# Reactor_Core.net
KiCad netlist of a schematic drawn in EAGLE
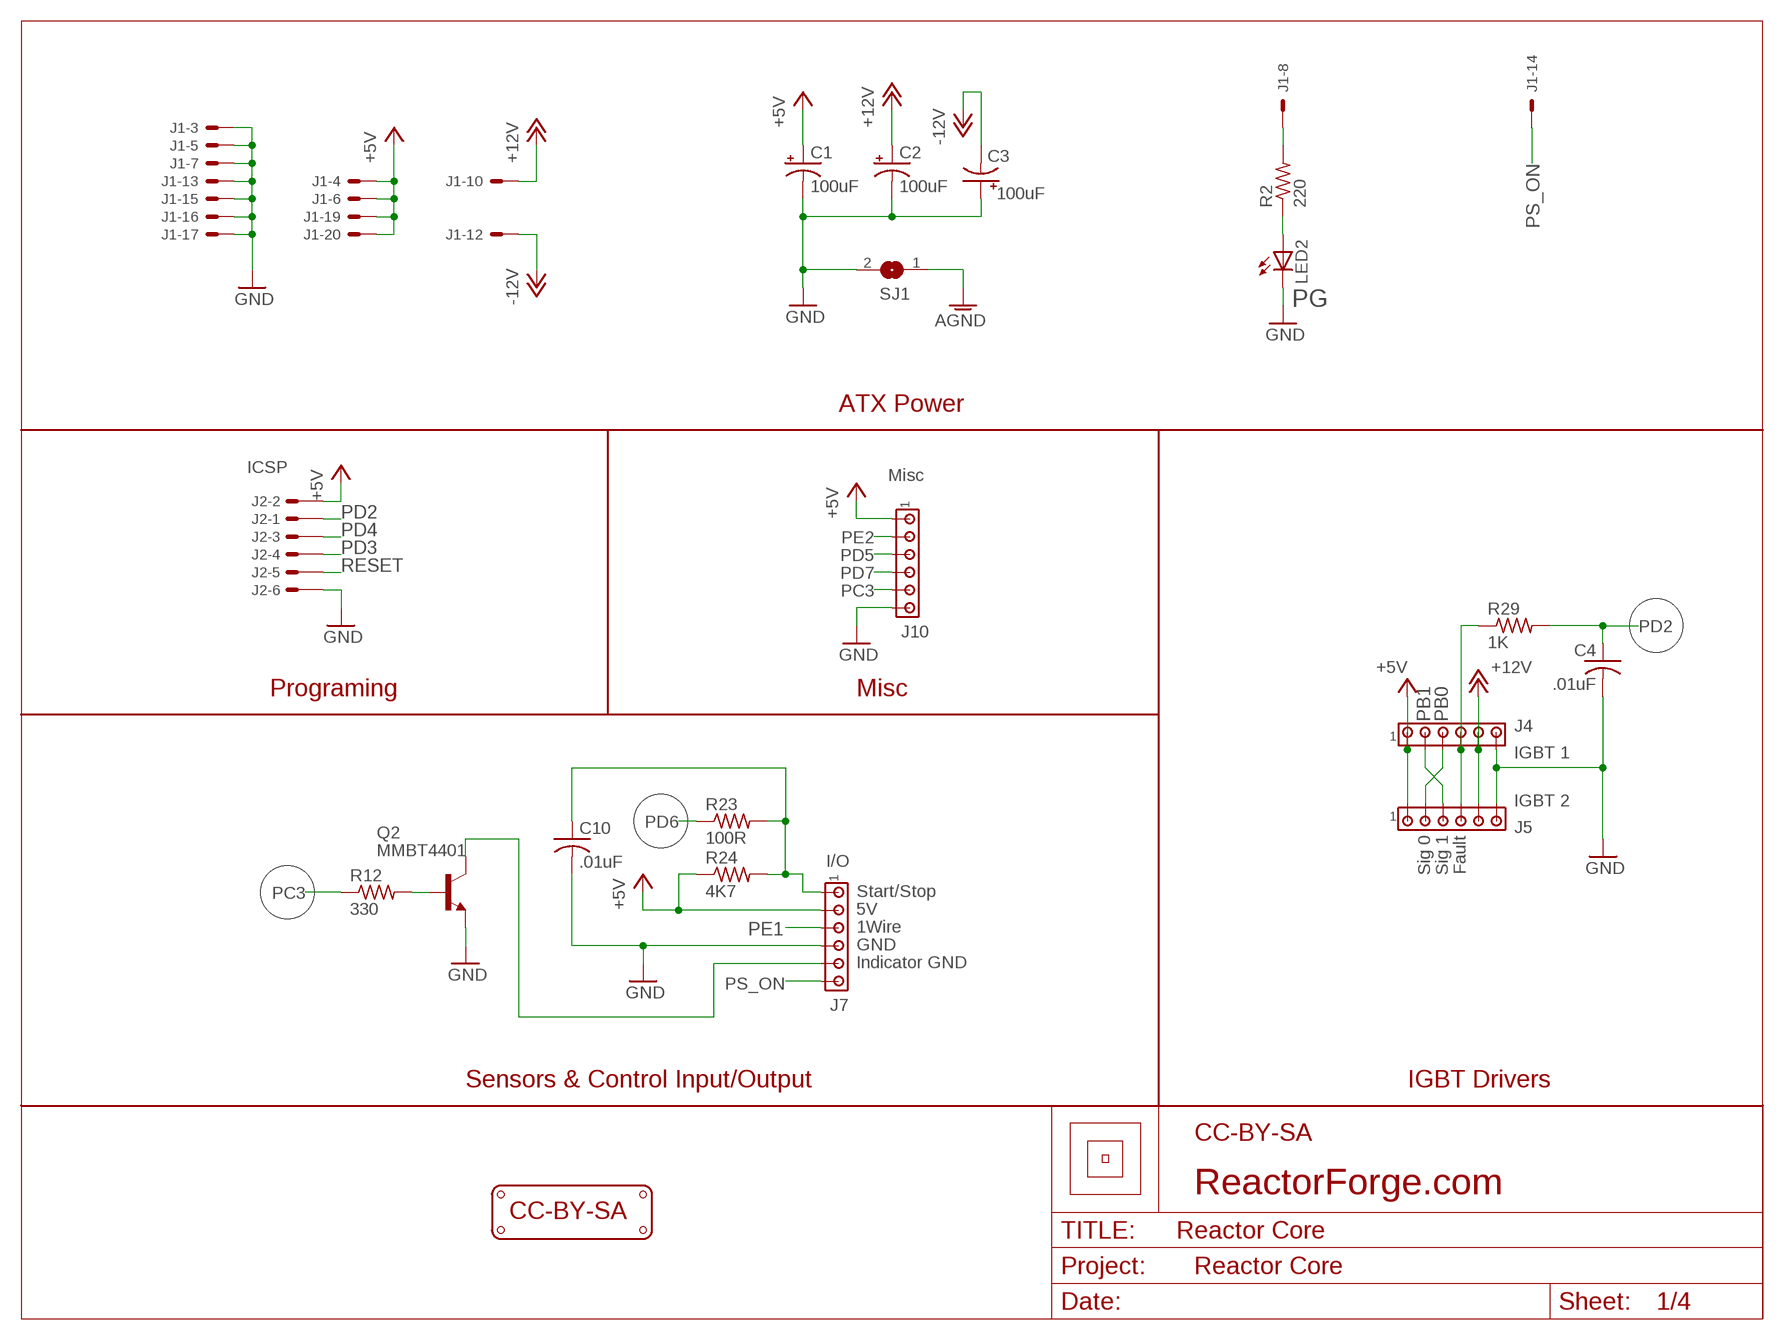
[diagram p0: schematic, sheet 1]
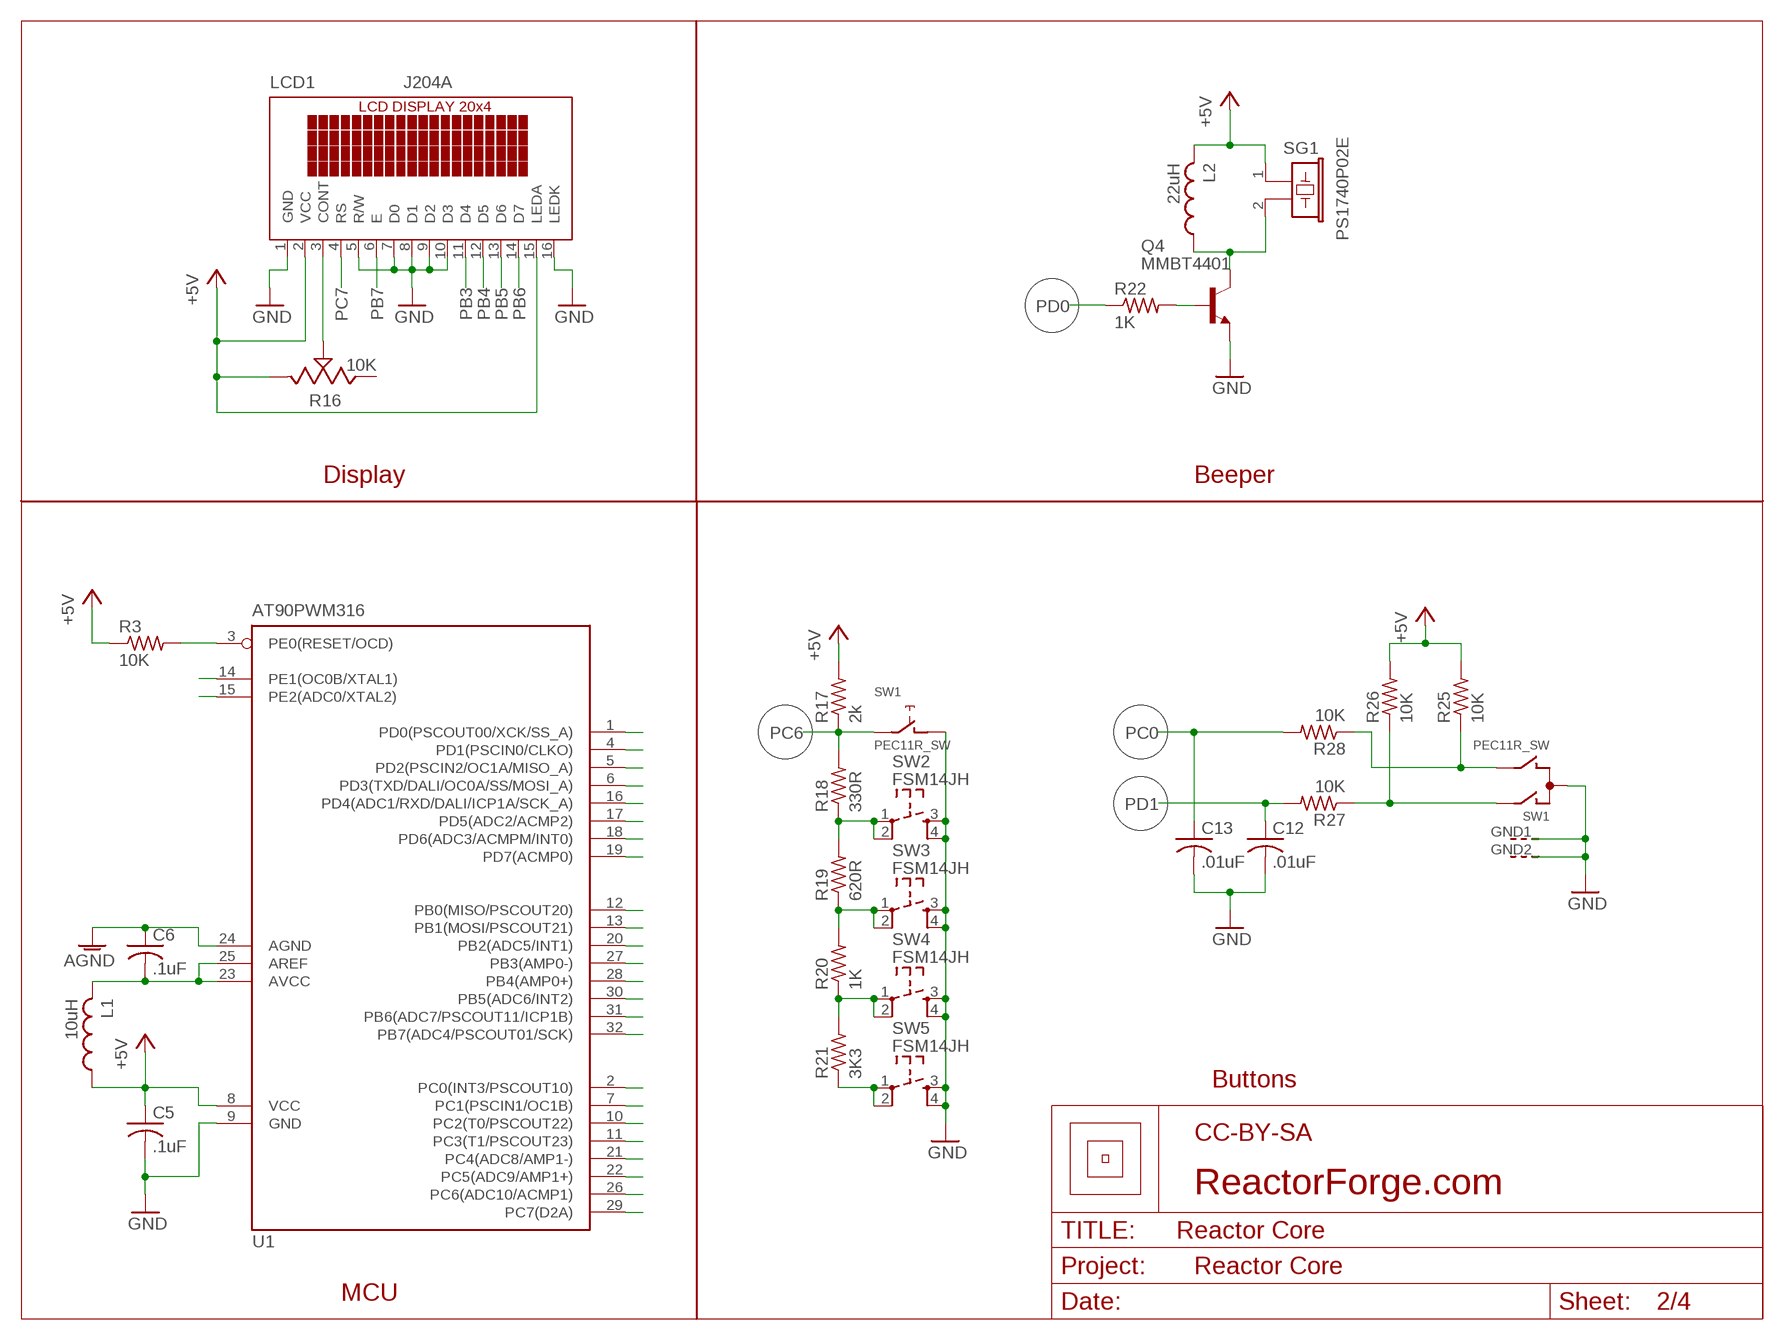
[diagram p1: schematic, sheet 2]
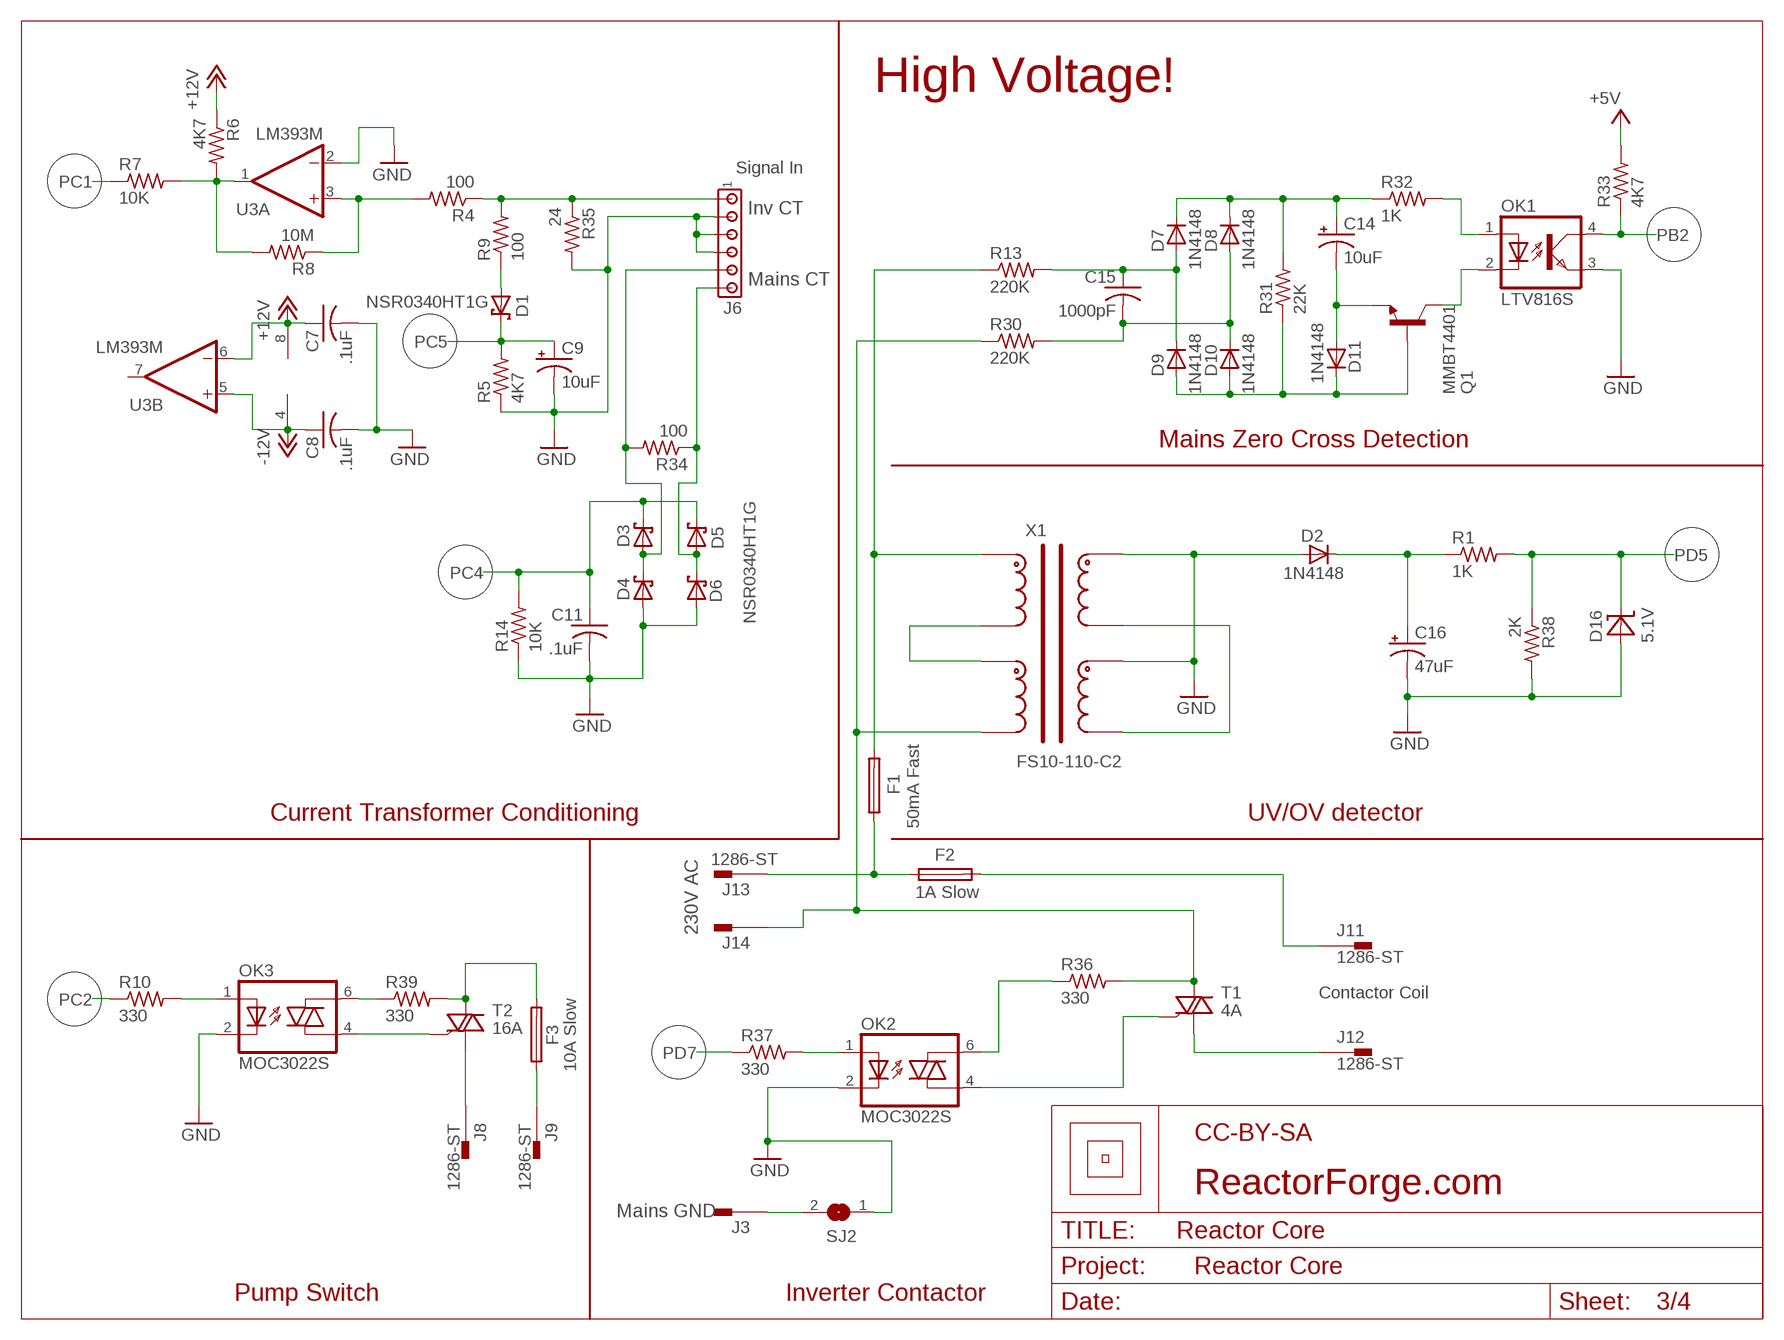
[diagram p2: schematic, sheet 3]
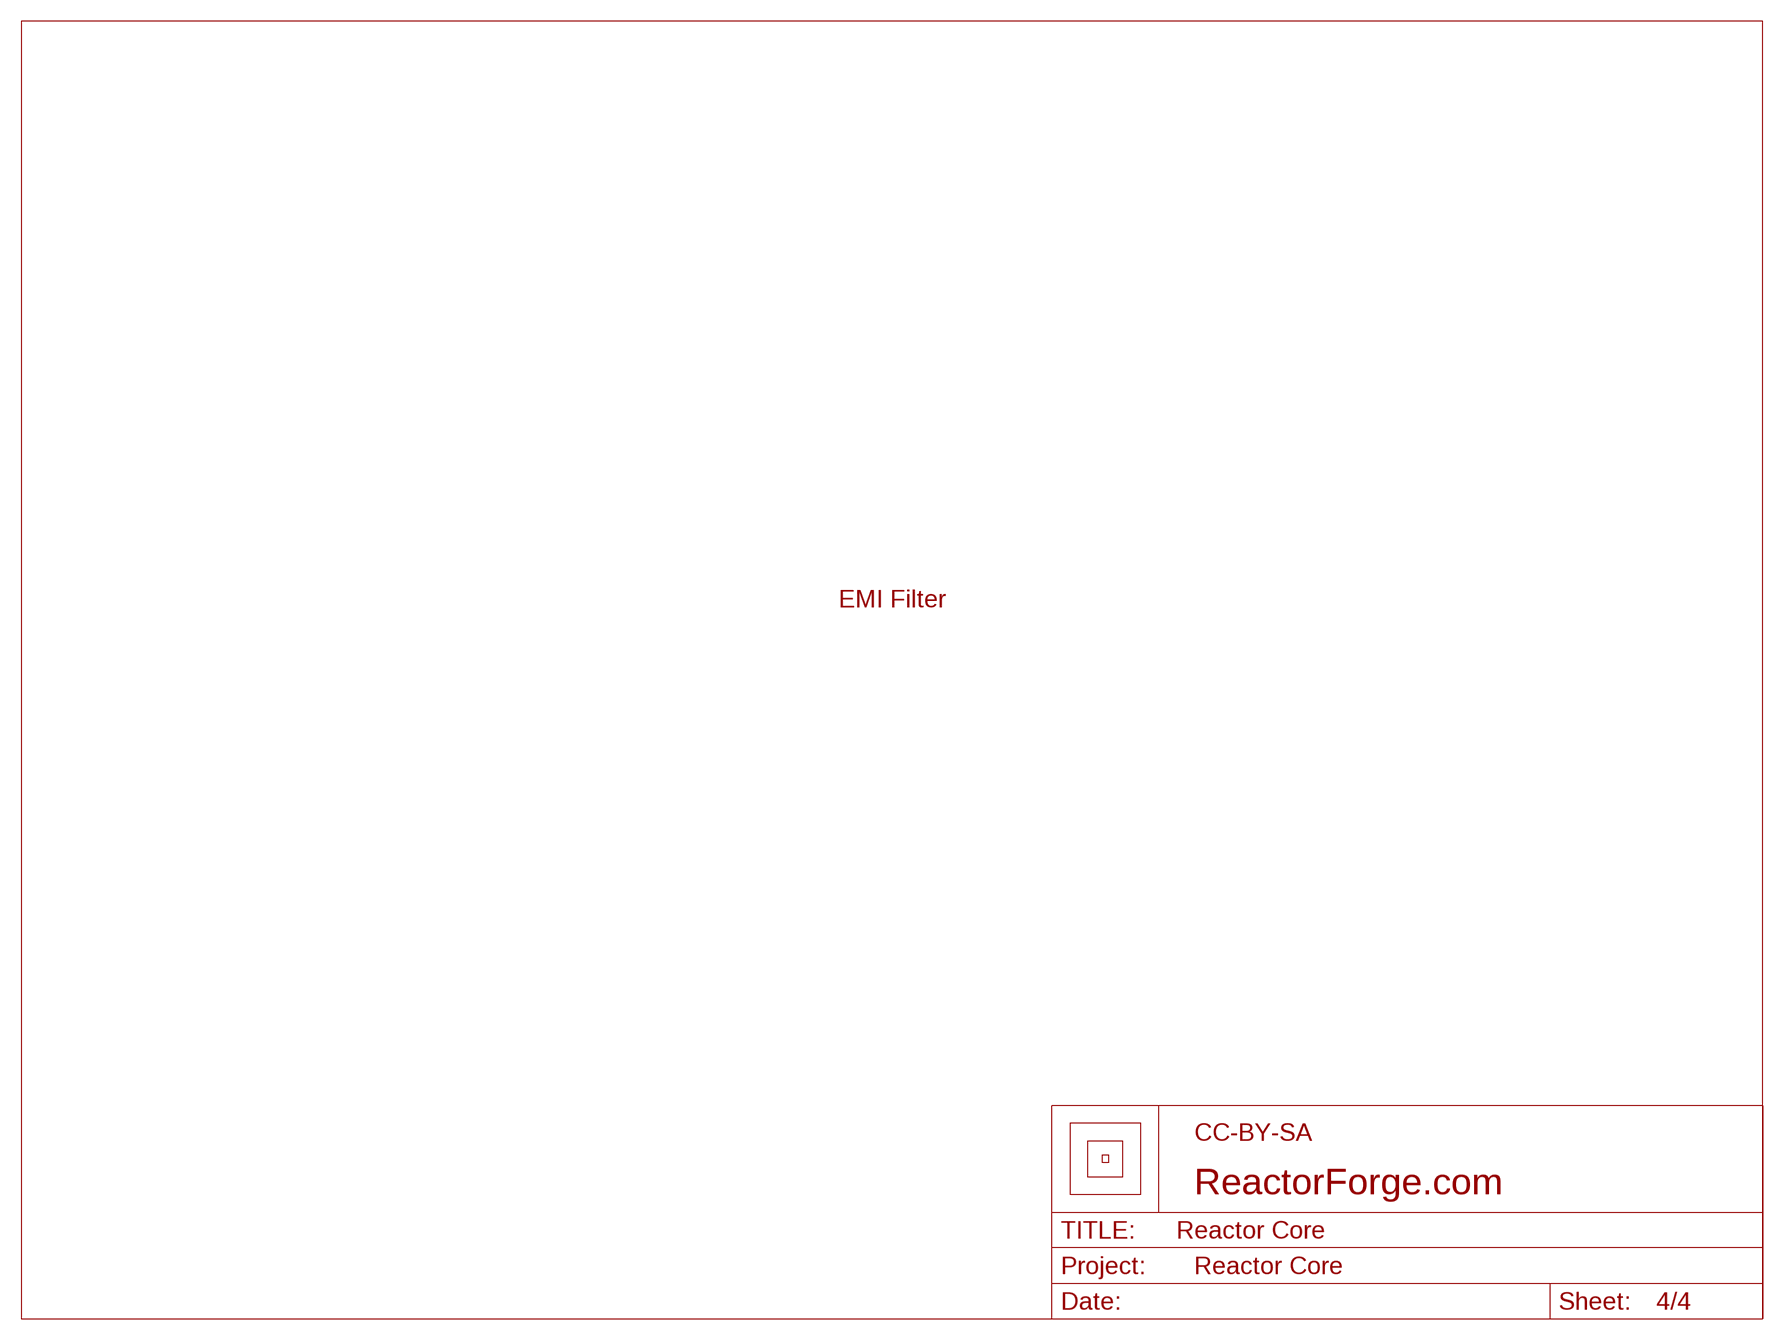
[diagram p3: schematic, sheet 4]

(export (version "E")
  (design (tool "Eeschema 10.0.6"))
  (components
    (comp (ref "C5")
      (value ".1uF")
      (footprint "eagle-import:C1206K")
      (libsource (lib "eagle-import") (part "C-USC1206K"))
    )
    (comp (ref "C6")
      (value ".1uF")
      (footprint "eagle-import:C1206K")
      (libsource (lib "eagle-import") (part "C-USC1206K"))
    )
    (comp (ref "C12")
      (value ".01uF")
      (footprint "eagle-import:C1206K")
      (libsource (lib "eagle-import") (part "C-USC1206K"))
    )
    (comp (ref "C13")
      (value ".01uF")
      (footprint "eagle-import:C1206K")
      (libsource (lib "eagle-import") (part "C-USC1206K"))
    )
    (comp (ref "L1")
      (value "10uH")
      (footprint "eagle-import:L3225P")
      (libsource (lib "eagle-import") (part "L-USL3225P"))
    )
    (comp (ref "L2")
      (value "22uH")
      (footprint "eagle-import:L3225P")
      (libsource (lib "eagle-import") (part "L-USL3225P"))
    )
    (comp (ref "LCD1")
      (value "J204A")
      (footprint "eagle-import:LCD-20X4")
      (libsource (lib "eagle-import") (part "J204A"))
    )
    (comp (ref "Q4")
      (value "MMBT4401")
      (footprint "eagle-import:SOT23")
      (libsource (lib "eagle-import") (part "MMBT4401"))
    )
    (comp (ref "R3")
      (value "10K")
      (footprint "eagle-import:R1206")
      (libsource (lib "eagle-import") (part "R-US_R1206"))
    )
    (comp (ref "R16")
      (value "10K")
      (footprint "eagle-import:TRIMMER_3314G")
      (libsource (lib "eagle-import") (part "TRIMMER_3314G"))
    )
    (comp (ref "R17")
      (value "2k")
      (footprint "eagle-import:R1206")
      (libsource (lib "eagle-import") (part "R-US_R1206"))
    )
    (comp (ref "R18")
      (value "330R")
      (footprint "eagle-import:R1206")
      (libsource (lib "eagle-import") (part "R-US_R1206"))
    )
    (comp (ref "R19")
      (value "620R")
      (footprint "eagle-import:R1206")
      (libsource (lib "eagle-import") (part "R-US_R1206"))
    )
    (comp (ref "R20")
      (value "1K")
      (footprint "eagle-import:R1206")
      (libsource (lib "eagle-import") (part "R-US_R1206"))
    )
    (comp (ref "R21")
      (value "3K3")
      (footprint "eagle-import:R1206")
      (libsource (lib "eagle-import") (part "R-US_R1206"))
    )
    (comp (ref "R22")
      (value "1K")
      (footprint "eagle-import:R1206")
      (libsource (lib "eagle-import") (part "R-US_R1206"))
    )
    (comp (ref "R25")
      (value "10K")
      (footprint "eagle-import:M1206")
      (libsource (lib "eagle-import") (part "R-US_M1206"))
    )
    (comp (ref "R26")
      (value "10K")
      (footprint "eagle-import:M1206")
      (libsource (lib "eagle-import") (part "R-US_M1206"))
    )
    (comp (ref "R27")
      (value "10K")
      (footprint "eagle-import:R1206")
      (libsource (lib "eagle-import") (part "R-US_R1206"))
    )
    (comp (ref "R28")
      (value "10K")
      (footprint "eagle-import:R1206")
      (libsource (lib "eagle-import") (part "R-US_R1206"))
    )
    (comp (ref "SG1")
      (value "PS1740P02E")
      (footprint "eagle-import:F_EE17P")
      (fields (field (name "MPN") "PS1740P02E"))
      (libsource (lib "eagle-import") (part "F/EE17P"))
    )
    (comp (ref "SW1")
      (value "PEC11R_SW")
      (footprint "eagle-import:BOURNS_PEC11R_SW")
      (fields (field (name "MF") "Bourns") (field (name "MPN") "PEC11R-4215K-S0012"))
      (libsource (lib "eagle-import") (part "PEC11R_SW"))
    )
    (comp (ref "SW2")
      (value "FSM14JH")
      (footprint "eagle-import:SW_TACTILE_TOP_ACTIVATED")
      (libsource (lib "eagle-import") (part "SW_TACTILE_TOP_ACTIVATED"))
    )
    (comp (ref "SW3")
      (value "FSM14JH")
      (footprint "eagle-import:SW_TACTILE_TOP_ACTIVATED")
      (libsource (lib "eagle-import") (part "SW_TACTILE_TOP_ACTIVATED"))
    )
    (comp (ref "SW4")
      (value "FSM14JH")
      (footprint "eagle-import:SW_TACTILE_TOP_ACTIVATED")
      (libsource (lib "eagle-import") (part "SW_TACTILE_TOP_ACTIVATED"))
    )
    (comp (ref "SW5")
      (value "FSM14JH")
      (footprint "eagle-import:SW_TACTILE_TOP_ACTIVATED")
      (libsource (lib "eagle-import") (part "SW_TACTILE_TOP_ACTIVATED"))
    )
    (comp (ref "U1")
      (value "AT90PWM316")
      (footprint "eagle-import:SOIC-32")
      (libsource (lib "eagle-import") (part "AT90PWM316"))
    )
    (comp (ref "C7")
      (value ".1uF")
      (footprint "eagle-import:C1206")
      (libsource (lib "eagle-import") (part "C-USC1206"))
    )
    (comp (ref "C8")
      (value ".1uF")
      (footprint "eagle-import:C1206")
      (libsource (lib "eagle-import") (part "C-USC1206"))
    )
    (comp (ref "C9")
      (value "10uF")
      (footprint "eagle-import:153CLV-0405")
      (libsource (lib "eagle-import") (part "CPOL-US153CLV-0405"))
    )
    (comp (ref "C11")
      (value ".1uF")
      (footprint "eagle-import:C1206")
      (libsource (lib "eagle-import") (part "C-USC1206"))
    )
    (comp (ref "C14")
      (value "10uF")
      (footprint "eagle-import:153CLV-0405")
      (libsource (lib "eagle-import") (part "CPOL-US153CLV-0405"))
    )
    (comp (ref "C15")
      (value "1000pF")
      (footprint "eagle-import:C1206")
      (libsource (lib "eagle-import") (part "C-USC1206"))
    )
    (comp (ref "C16")
      (value "47uF")
      (footprint "eagle-import:153CLV-0605")
      (libsource (lib "eagle-import") (part "CPOL-US153CLV-0605"))
    )
    (comp (ref "D1")
      (value "NSR0340HT1G")
      (footprint "eagle-import:SOD-323")
      (libsource (lib "eagle-import") (part "NSR0340HT1G"))
    )
    (comp (ref "D2")
      (value "1N4148")
      (footprint "eagle-import:SOD-123")
      (libsource (lib "eagle-import") (part "1N4148"))
    )
    (comp (ref "D3")
      (value "NSR0340HT1G")
      (footprint "eagle-import:SOD-323")
      (libsource (lib "eagle-import") (part "NSR0340HT1G"))
    )
    (comp (ref "D4")
      (value "NSR0340HT1G")
      (footprint "eagle-import:SOD-323")
      (libsource (lib "eagle-import") (part "NSR0340HT1G"))
    )
    (comp (ref "D5")
      (value "NSR0340HT1G")
      (footprint "eagle-import:SOD-323")
      (libsource (lib "eagle-import") (part "NSR0340HT1G"))
    )
    (comp (ref "D6")
      (value "NSR0340HT1G")
      (footprint "eagle-import:SOD-323")
      (libsource (lib "eagle-import") (part "NSR0340HT1G"))
    )
    (comp (ref "D7")
      (value "1N4148")
      (footprint "eagle-import:SOD-123")
      (libsource (lib "eagle-import") (part "1N4148"))
    )
    (comp (ref "D8")
      (value "1N4148")
      (footprint "eagle-import:SOD-123")
      (libsource (lib "eagle-import") (part "1N4148"))
    )
    (comp (ref "D9")
      (value "1N4148")
      (footprint "eagle-import:SOD-123")
      (libsource (lib "eagle-import") (part "1N4148"))
    )
    (comp (ref "D10")
      (value "1N4148")
      (footprint "eagle-import:SOD-123")
      (libsource (lib "eagle-import") (part "1N4148"))
    )
    (comp (ref "D11")
      (value "1N4148")
      (footprint "eagle-import:SOD-123")
      (libsource (lib "eagle-import") (part "1N4148"))
    )
    (comp (ref "D16")
      (value "5.1V")
      (footprint "eagle-import:SOD-323")
      (fields (field (name "MF") "5.1V 200MW") (field (name "MPN") "MM3Z5V1ST1G"))
      (libsource (lib "eagle-import") (part "MM3Z5V1ST1G"))
    )
    (comp (ref "F1")
      (value "50mA Fast")
      (footprint "eagle-import:TR5")
      (fields (field (name "MF") "Bel Fuse Inc") (field (name "MPN") "MRF 50"))
      (libsource (lib "eagle-import") (part "TR5"))
    )
    (comp (ref "F2")
      (value "1A Slow")
      (footprint "eagle-import:FC211-5X20")
      (libsource (lib "eagle-import") (part "FC211-5X20"))
    )
    (comp (ref "F3")
      (value "10A Slow")
      (footprint "eagle-import:FC211-5X20")
      (libsource (lib "eagle-import") (part "FC211-5X20"))
    )
    (comp (ref "J3")
      (value "1286-ST")
      (footprint "eagle-import:62409-1")
      (fields (field (name "OC_FARNELL") "unknown") (field (name "OC_NEWARK") "unknown"))
      (libsource (lib "eagle-import") (part "PIN262409-1"))
    )
    (comp (ref "J6")
      (value "Signal In")
      (footprint "eagle-import:10X06MTA")
      (libsource (lib "eagle-import") (part "MTA06-100"))
    )
    (comp (ref "J8")
      (value "1286-ST")
      (footprint "eagle-import:62409-1")
      (libsource (lib "eagle-import") (part "PIN262409-1"))
    )
    (comp (ref "J9")
      (value "1286-ST")
      (footprint "eagle-import:62409-1")
      (libsource (lib "eagle-import") (part "PIN262409-1"))
    )
    (comp (ref "J11")
      (value "1286-ST")
      (footprint "eagle-import:62409-1")
      (fields (field (name "OC_FARNELL") "unknown") (field (name "OC_NEWARK") "unknown"))
      (libsource (lib "eagle-import") (part "PIN262409-1"))
    )
    (comp (ref "J12")
      (value "1286-ST")
      (footprint "eagle-import:62409-1")
      (fields (field (name "OC_FARNELL") "unknown") (field (name "OC_NEWARK") "unknown"))
      (libsource (lib "eagle-import") (part "PIN262409-1"))
    )
    (comp (ref "J13")
      (value "1286-ST")
      (footprint "eagle-import:62409-1")
      (fields (field (name "OC_FARNELL") "unknown") (field (name "OC_NEWARK") "unknown"))
      (libsource (lib "eagle-import") (part "PIN262409-1"))
    )
    (comp (ref "J14")
      (value "1286-ST")
      (footprint "eagle-import:62409-1")
      (fields (field (name "OC_FARNELL") "unknown") (field (name "OC_NEWARK") "unknown"))
      (libsource (lib "eagle-import") (part "PIN262409-1"))
    )
    (comp (ref "OK1")
      (value "LTV816S")
      (footprint "eagle-import:SMD4")
      (libsource (lib "eagle-import") (part "LTV816S"))
    )
    (comp (ref "OK2")
      (value "MOC3022S")
      (footprint "eagle-import:6-SMD")
      (fields (field (name "MF") "Lite-On Inc"))
      (libsource (lib "eagle-import") (part "MOC3022S"))
    )
    (comp (ref "OK3")
      (value "MOC3022S")
      (footprint "eagle-import:6-SMD")
      (fields
        (field (name "MF") "Lite-On Inc")
        (field (name "MF_1") "Lite-On Inc")
        (field (name "MPN") "MOC3022S")
        (field (name "PN_DIGI-KEY") "160-1377-5-ND")
      )
      (libsource (lib "eagle-import") (part "MOC3022S"))
    )
    (comp (ref "Q1")
      (value "MMBT4401")
      (footprint "eagle-import:SOT23")
      (libsource (lib "eagle-import") (part "MMBT4401"))
    )
    (comp (ref "R1")
      (value "1K")
      (footprint "eagle-import:R1206")
      (fields (field (name "MF") "Stackpole Electronics Inc") (field (name "MPN") "RNCP1206FTD100R"))
      (libsource (lib "eagle-import") (part "R-US_R1206"))
    )
    (comp (ref "R4")
      (value "100")
      (footprint "eagle-import:R1206")
      (libsource (lib "eagle-import") (part "R-US_R1206"))
    )
    (comp (ref "R5")
      (value "4K7")
      (footprint "eagle-import:R1206")
      (libsource (lib "eagle-import") (part "R-US_R1206"))
    )
    (comp (ref "R6")
      (value "4K7")
      (footprint "eagle-import:R1206")
      (libsource (lib "eagle-import") (part "R-US_R1206"))
    )
    (comp (ref "R7")
      (value "10K")
      (footprint "eagle-import:R1206")
      (libsource (lib "eagle-import") (part "R-US_R1206"))
    )
    (comp (ref "R8")
      (value "10M")
      (footprint "eagle-import:R1206")
      (libsource (lib "eagle-import") (part "R-US_R1206"))
    )
    (comp (ref "R9")
      (value "100")
      (footprint "eagle-import:R1206")
      (libsource (lib "eagle-import") (part "R-US_R1206"))
    )
    (comp (ref "R10")
      (value "330")
      (footprint "eagle-import:M1206")
      (libsource (lib "eagle-import") (part "R-US_M1206"))
    )
    (comp (ref "R13")
      (value "220K")
      (footprint "eagle-import:R1206")
      (libsource (lib "eagle-import") (part "R-US_R1206"))
    )
    (comp (ref "R14")
      (value "10K")
      (footprint "eagle-import:R1206")
      (libsource (lib "eagle-import") (part "R-US_R1206"))
    )
    (comp (ref "R30")
      (value "220K")
      (footprint "eagle-import:R1206")
      (libsource (lib "eagle-import") (part "R-US_R1206"))
    )
    (comp (ref "R31")
      (value "22K")
      (footprint "eagle-import:R1206")
      (libsource (lib "eagle-import") (part "R-US_R1206"))
    )
    (comp (ref "R32")
      (value "1K")
      (footprint "eagle-import:R1206")
      (libsource (lib "eagle-import") (part "R-US_R1206"))
    )
    (comp (ref "R33")
      (value "4K7")
      (footprint "eagle-import:R1206")
      (libsource (lib "eagle-import") (part "R-US_R1206"))
    )
    (comp (ref "R34")
      (value "100")
      (footprint "eagle-import:R1206")
      (fields (field (name "MF") "Stackpole Electronics Inc") (field (name "MPN") "RNCP1206FTD100R"))
      (libsource (lib "eagle-import") (part "R-US_R1206"))
    )
    (comp (ref "R35")
      (value "24")
      (footprint "eagle-import:R2512")
      (fields (field (name "MF") "TE Connectivity") (field (name "MPN") "352124RFT"))
      (libsource (lib "eagle-import") (part "R-US_R2512"))
    )
    (comp (ref "R36")
      (value "330")
      (footprint "eagle-import:R1206")
      (libsource (lib "eagle-import") (part "R-US_R1206"))
    )
    (comp (ref "R37")
      (value "330")
      (footprint "eagle-import:R1206")
      (libsource (lib "eagle-import") (part "R-US_R1206"))
    )
    (comp (ref "R38")
      (value "2K")
      (footprint "eagle-import:R1206")
      (fields (field (name "MF") "Stackpole Electronics Inc") (field (name "MPN") "RNCP1206FTD100R"))
      (libsource (lib "eagle-import") (part "R-US_R1206"))
    )
    (comp (ref "R39")
      (value "330")
      (footprint "eagle-import:R1206")
      (libsource (lib "eagle-import") (part "R-US_R1206"))
    )
    (comp (ref "SJ2") (value "0") (footprint "eagle-import:SJ") (libsource (lib "eagle-import") (part "SJ")))
    (comp (ref "T1")
      (value "4A")
      (footprint "eagle-import:DPAK-TRIAC")
      (fields (field (name "MF") "STMicroelectronics") (field (name "MPN") "T435-600B-TR"))
      (libsource (lib "eagle-import") (part "T435-600B-TR"))
    )
    (comp (ref "T2")
      (value "16A")
      (footprint "eagle-import:DPAK-TRIAC")
      (fields
        (field (name "MF") "STMicroelectronics")
        (field (name "MPN") "T435-600B-TR")
        (field (name "MF_1") "STMicroelectronics")
        (field (name "MPN_1") "T1635-700G-TR")
        (field (name "PN_DIGI-KEY") "497-4433-1-ND")
      )
      (libsource (lib "eagle-import") (part "T435-600B-TR"))
    )
    (comp (ref "U3")
      (value "LM393M")
      (footprint "eagle-import:SO08")
      (fields
        (field (name "MF") "Fairchild Semiconductor")
        (field (name "MPN") "LM393M")
        (field (name "PN_DIGI-KEY") "LM393MFS-ND")
      )
      (libsource (lib "eagle-import") (part "LM393D"))
    )
    (comp (ref "X1")
      (value "FS10-110-C2")
      (footprint "eagle-import:FS10-110-C2")
      (fields (field (name "MF") "Triad Magnetics") (field (name "MPN") "FS10-110-C2-B "))
      (libsource (lib "eagle-import") (part "FS10-110-C2"))
    )
    (comp (ref "C1")
      (value "100uF")
      (footprint "eagle-import:E2-5")
      (libsource (lib "eagle-import") (part "CPOL-USE2-5"))
    )
    (comp (ref "C2")
      (value "100uF")
      (footprint "eagle-import:E2-5")
      (libsource (lib "eagle-import") (part "CPOL-USE2-5"))
    )
    (comp (ref "C3")
      (value "100uF")
      (footprint "eagle-import:E2-5")
      (libsource (lib "eagle-import") (part "CPOL-USE2-5"))
    )
    (comp (ref "C4")
      (value ".01uF")
      (footprint "eagle-import:C1206")
      (libsource (lib "eagle-import") (part "C-USC1206"))
    )
    (comp (ref "C10")
      (value ".01uF")
      (footprint "eagle-import:C1206K")
      (libsource (lib "eagle-import") (part "C-USC1206K"))
    )
    (comp (ref "J1")
      (value "ATX Power")
      (footprint "eagle-import:5566-20")
      (fields (field (name "MPN") "39-29-9206") (field (name "PN_DIGI-KEY") "2M3873-ND"))
      (libsource (lib "eagle-import") (part "5566-20"))
    )
    (comp (ref "J2")
      (value "ICSP")
      (footprint "eagle-import:057-006-1")
      (libsource (lib "eagle-import") (part "057-006-1"))
    )
    (comp (ref "J4")
      (value "IGBT 1")
      (footprint "eagle-import:10X06MTA")
      (libsource (lib "eagle-import") (part "MTA06-100"))
    )
    (comp (ref "J5")
      (value "IGBT 2")
      (footprint "eagle-import:10X06MTA")
      (libsource (lib "eagle-import") (part "MTA06-100"))
    )
    (comp (ref "J7")
      (value "I/O")
      (footprint "eagle-import:10X06MTA")
      (libsource (lib "eagle-import") (part "MTA06-100"))
    )
    (comp (ref "J10")
      (value "Misc")
      (footprint "eagle-import:10X06MTA")
      (libsource (lib "eagle-import") (part "MTA06-100"))
    )
    (comp (ref "LED2")
      (value "LEDCHIPLED_1206")
      (footprint "eagle-import:CHIPLED_1206")
      (libsource (lib "eagle-import") (part "LEDCHIPLED_1206"))
    )
    (comp (ref "LOGO1")
      (value "LOGO_CC-BY-SA")
      (footprint "eagle-import:LOGO_CC-BY-SA")
      (libsource (lib "eagle-import") (part "LOGO_CC-BY-SA"))
    )
    (comp (ref "Q2")
      (value "MMBT4401")
      (footprint "eagle-import:SOT23")
      (libsource (lib "eagle-import") (part "MMBT4401"))
    )
    (comp (ref "R2")
      (value "220")
      (footprint "eagle-import:R1206")
      (libsource (lib "eagle-import") (part "R-US_R1206"))
    )
    (comp (ref "R12")
      (value "330")
      (footprint "eagle-import:R1206")
      (libsource (lib "eagle-import") (part "R-US_R1206"))
    )
    (comp (ref "R23")
      (value "100R")
      (footprint "eagle-import:R1206")
      (libsource (lib "eagle-import") (part "R-US_R1206"))
    )
    (comp (ref "R24")
      (value "4K7")
      (footprint "eagle-import:R1206")
      (libsource (lib "eagle-import") (part "R-US_R1206"))
    )
    (comp (ref "R29")
      (value "1K")
      (footprint "eagle-import:R1206")
      (libsource (lib "eagle-import") (part "R-US_R1206"))
    )
    (comp (ref "SJ1") (value "0") (footprint "eagle-import:SJ") (libsource (lib "eagle-import") (part "SJ")))
  )
  (nets
    (net (code "1") (name "+5V") (class "Default")
      (node (ref "C1") (pin "+") (pinfunction "+_+") (pintype "passive"))
      (node (ref "C5") (pin "1") (pinfunction "1_1") (pintype "passive"))
      (node (ref "J1") (pin "19") (pinfunction "S_19") (pintype "passive"))
      (node (ref "J1") (pin "20") (pinfunction "S_20") (pintype "passive"))
      (node (ref "J1") (pin "4") (pinfunction "S_4") (pintype "passive"))
      (node (ref "J1") (pin "6") (pinfunction "S_6") (pintype "passive"))
      (node (ref "J10") (pin "6") (pinfunction "1_6") (pintype "passive"))
      (node (ref "J2") (pin "2") (pinfunction "S_2") (pintype "passive"))
      (node (ref "J4") (pin "6") (pinfunction "1_6") (pintype "passive"))
      (node (ref "J5") (pin "6") (pinfunction "1_6") (pintype "passive"))
      (node (ref "J7") (pin "5") (pinfunction "2_5") (pintype "passive"))
      (node (ref "L1") (pin "1") (pinfunction "1_1") (pintype "passive"))
      (node (ref "L2") (pin "2") (pinfunction "2_2") (pintype "passive"))
      (node (ref "LCD1") (pin "15") (pinfunction "LEDA_15") (pintype "input"))
      (node (ref "LCD1") (pin "2") (pinfunction "VCC_2") (pintype "power_in"))
      (node (ref "R16") (pin "3") (pinfunction "3_3") (pintype "passive"))
      (node (ref "R17") (pin "2") (pinfunction "2_2") (pintype "passive"))
      (node (ref "R24") (pin "1") (pinfunction "1_1") (pintype "passive"))
      (node (ref "R25") (pin "2") (pinfunction "2_2") (pintype "passive"))
      (node (ref "R26") (pin "2") (pinfunction "2_2") (pintype "passive"))
      (node (ref "R3") (pin "1") (pinfunction "1_1") (pintype "passive"))
      (node (ref "R33") (pin "2") (pinfunction "2_2") (pintype "passive"))
      (node (ref "SG1") (pin "1") (pinfunction "1_1") (pintype "passive"))
      (node (ref "U1") (pin "8") (pinfunction "VCC_8") (pintype "power_in"))
    )
    (net (code "2") (name "+12V") (class "Default")
      (node (ref "C2") (pin "+") (pinfunction "+_+") (pintype "passive"))
      (node (ref "C7") (pin "1") (pinfunction "1_1") (pintype "passive"))
      (node (ref "J1") (pin "10") (pinfunction "S_10") (pintype "passive"))
      (node (ref "J4") (pin "2") (pinfunction "5_2") (pintype "passive"))
      (node (ref "J5") (pin "2") (pinfunction "5_2") (pintype "passive"))
      (node (ref "R6") (pin "1") (pinfunction "1_1") (pintype "passive"))
      (node (ref "U3") (pin "6") (pinfunction "-IN_6") (pintype "input"))
      (node (ref "U3") (pin "8") (pinfunction "V+_8") (pintype "power_in"))
    )
    (net (code "3") (name "-12V") (class "Default")
      (node (ref "C3") (pin "-") (pinfunction "-_-") (pintype "passive"))
      (node (ref "C8") (pin "1") (pinfunction "1_1") (pintype "passive"))
      (node (ref "J1") (pin "12") (pinfunction "S_12") (pintype "passive"))
      (node (ref "U3") (pin "4") (pinfunction "V-_4") (pintype "power_in"))
      (node (ref "U3") (pin "5") (pinfunction "+IN_5") (pintype "input"))
    )
    (net (code "4") (name "AGND") (class "Default")
      (node (ref "C6") (pin "1") (pinfunction "1_1") (pintype "passive"))
      (node (ref "SJ1") (pin "1") (pinfunction "1_1") (pintype "passive"))
      (node (ref "U1") (pin "24") (pinfunction "AGND_24") (pintype "power_in"))
    )
    (net (code "5") (name "GND") (class "Default")
      (node (ref "C1") (pin "-") (pinfunction "-_-") (pintype "passive"))
      (node (ref "C10") (pin "2") (pinfunction "2_2") (pintype "passive"))
      (node (ref "C11") (pin "2") (pinfunction "2_2") (pintype "passive"))
      (node (ref "C12") (pin "2") (pinfunction "2_2") (pintype "passive"))
      (node (ref "C13") (pin "2") (pinfunction "2_2") (pintype "passive"))
      (node (ref "C16") (pin "-") (pinfunction "-_-") (pintype "passive"))
      (node (ref "C2") (pin "-") (pinfunction "-_-") (pintype "passive"))
      (node (ref "C3") (pin "+") (pinfunction "+_+") (pintype "passive"))
      (node (ref "C4") (pin "2") (pinfunction "2_2") (pintype "passive"))
      (node (ref "C5") (pin "2") (pinfunction "2_2") (pintype "passive"))
      (node (ref "C7") (pin "2") (pinfunction "2_2") (pintype "passive"))
      (node (ref "C8") (pin "2") (pinfunction "2_2") (pintype "passive"))
      (node (ref "C9") (pin "-") (pinfunction "-_-") (pintype "passive"))
      (node (ref "D16") (pin "A") (pinfunction "A_A") (pintype "passive"))
      (node (ref "D2") (pin "A") (pinfunction "A_A") (pintype "passive"))
      (node (ref "D4") (pin "A") (pinfunction "A_A") (pintype "passive"))
      (node (ref "D6") (pin "A") (pinfunction "A_A") (pintype "passive"))
      (node (ref "J1") (pin "13") (pinfunction "S_13") (pintype "passive"))
      (node (ref "J1") (pin "15") (pinfunction "S_15") (pintype "passive"))
      (node (ref "J1") (pin "16") (pinfunction "S_16") (pintype "passive"))
      (node (ref "J1") (pin "17") (pinfunction "S_17") (pintype "passive"))
      (node (ref "J1") (pin "3") (pinfunction "S_3") (pintype "passive"))
      (node (ref "J1") (pin "5") (pinfunction "S_5") (pintype "passive"))
      (node (ref "J1") (pin "7") (pinfunction "S_7") (pintype "passive"))
      (node (ref "J10") (pin "1") (pinfunction "6_1") (pintype "passive"))
      (node (ref "J2") (pin "6") (pinfunction "S_6") (pintype "passive"))
      (node (ref "J4") (pin "1") (pinfunction "6_1") (pintype "passive"))
      (node (ref "J5") (pin "1") (pinfunction "6_1") (pintype "passive"))
      (node (ref "J6") (pin "3") (pinfunction "4_3") (pintype "passive"))
      (node (ref "J6") (pin "4") (pinfunction "3_4") (pintype "passive"))
      (node (ref "J6") (pin "5") (pinfunction "2_5") (pintype "passive"))
      (node (ref "J7") (pin "3") (pinfunction "4_3") (pintype "passive"))
      (node (ref "LCD1") (pin "1") (pinfunction "GND_1") (pintype "power_in"))
      (node (ref "LCD1") (pin "10") (pinfunction "D3_10") (pintype "input"))
      (node (ref "LCD1") (pin "16") (pinfunction "LEDK_16") (pintype "input"))
      (node (ref "LCD1") (pin "5") (pinfunction "R/W_5") (pintype "input"))
      (node (ref "LCD1") (pin "7") (pinfunction "D0_7") (pintype "input"))
      (node (ref "LCD1") (pin "8") (pinfunction "D1_8") (pintype "input"))
      (node (ref "LCD1") (pin "9") (pinfunction "D2_9") (pintype "input"))
      (node (ref "LED2") (pin "C") (pinfunction "C_C") (pintype "passive"))
      (node (ref "OK1") (pin "3") (pinfunction "EMIT_3") (pintype "passive"))
      (node (ref "OK2") (pin "2") (pinfunction "C_2") (pintype "passive"))
      (node (ref "OK3") (pin "2") (pinfunction "C_2") (pintype "passive"))
      (node (ref "Q2") (pin "2") (pinfunction "E_2") (pintype "passive"))
      (node (ref "Q4") (pin "2") (pinfunction "E_2") (pintype "passive"))
      (node (ref "R14") (pin "1") (pinfunction "1_1") (pintype "passive"))
      (node (ref "R35") (pin "2") (pinfunction "2_2") (pintype "passive"))
      (node (ref "R38") (pin "2") (pinfunction "2_2") (pintype "passive"))
      (node (ref "R5") (pin "1") (pinfunction "1_1") (pintype "passive"))
      (node (ref "SJ1") (pin "2") (pinfunction "2_2") (pintype "passive"))
      (node (ref "SJ2") (pin "1") (pinfunction "1_1") (pintype "passive"))
      (node (ref "SW1") (pin "C") (pinfunction "C_C") (pintype "passive"))
      (node (ref "SW1") (pin "GND1") (pinfunction "G_GND1") (pintype "passive"))
      (node (ref "SW1") (pin "GND2") (pinfunction "G_GND2") (pintype "passive"))
      (node (ref "SW1") (pin "S") (pinfunction "1_S") (pintype "passive"))
      (node (ref "SW2") (pin "3") (pinfunction "3_3") (pintype "passive"))
      (node (ref "SW2") (pin "4") (pinfunction "4_4") (pintype "passive"))
      (node (ref "SW3") (pin "3") (pinfunction "3_3") (pintype "passive"))
      (node (ref "SW3") (pin "4") (pinfunction "4_4") (pintype "passive"))
      (node (ref "SW4") (pin "3") (pinfunction "3_3") (pintype "passive"))
      (node (ref "SW4") (pin "4") (pinfunction "4_4") (pintype "passive"))
      (node (ref "SW5") (pin "3") (pinfunction "3_3") (pintype "passive"))
      (node (ref "SW5") (pin "4") (pinfunction "4_4") (pintype "passive"))
      (node (ref "U1") (pin "9") (pinfunction "GND_9") (pintype "power_in"))
      (node (ref "U3") (pin "2") (pinfunction "-IN_2") (pintype "input"))
      (node (ref "X1") (pin "P$5") (pinfunction "P$5_P$5") (pintype "bidirectional"))
      (node (ref "X1") (pin "P$7") (pinfunction "P$7_P$7") (pintype "bidirectional"))
    )
    (net (code "6") (name "Net-(C14-Pad+)") (class "Default")
      (node (ref "C14") (pin "+") (pinfunction "+_+") (pintype "passive"))
      (node (ref "D7") (pin "C") (pinfunction "C_C") (pintype "passive"))
      (node (ref "D8") (pin "C") (pinfunction "C_C") (pintype "passive"))
      (node (ref "R31") (pin "2") (pinfunction "2_2") (pintype "passive"))
      (node (ref "R32") (pin "1") (pinfunction "1_1") (pintype "passive"))
    )
    (net (code "7") (name "Net-(C15-Pad1)") (class "Default")
      (node (ref "C15") (pin "1") (pinfunction "1_1") (pintype "passive"))
      (node (ref "D7") (pin "A") (pinfunction "A_A") (pintype "passive"))
      (node (ref "D9") (pin "C") (pinfunction "C_C") (pintype "passive"))
      (node (ref "R13") (pin "2") (pinfunction "2_2") (pintype "passive"))
    )
    (net (code "8") (name "Net-(C15-Pad2)") (class "Default")
      (node (ref "C15") (pin "2") (pinfunction "2_2") (pintype "passive"))
      (node (ref "D10") (pin "C") (pinfunction "C_C") (pintype "passive"))
      (node (ref "D8") (pin "A") (pinfunction "A_A") (pintype "passive"))
      (node (ref "R30") (pin "2") (pinfunction "2_2") (pintype "passive"))
    )
    (net (code "9") (name "Net-(C16-Pad+)") (class "Default")
      (node (ref "C16") (pin "+") (pinfunction "+_+") (pintype "passive"))
      (node (ref "D2") (pin "C") (pinfunction "C_C") (pintype "passive"))
      (node (ref "R1") (pin "1") (pinfunction "1_1") (pintype "passive"))
    )
    (net (code "10") (name "Net-(D1-PadA)") (class "Default")
      (node (ref "D1") (pin "A") (pinfunction "A_A") (pintype "passive"))
      (node (ref "R9") (pin "1") (pinfunction "1_1") (pintype "passive"))
    )
    (net (code "11") (name "Net-(F1-Pad1)") (class "Default")
      (node (ref "F1") (pin "1") (pinfunction "1_1") (pintype "passive"))
      (node (ref "F2") (pin "1A") (pinfunction "1_1A") (pintype "passive"))
      (node (ref "F2") (pin "1B") (pinfunction "1_1B") (pintype "passive"))
      (node (ref "J13") (pin "A1") (pinfunction "1_A1") (pintype "passive"))
      (node (ref "J13") (pin "A2") (pinfunction "1_A2") (pintype "passive"))
    )
    (net (code "12") (name "Net-(F1-Pad2)") (class "Default")
      (node (ref "F1") (pin "2") (pinfunction "2_2") (pintype "passive"))
      (node (ref "R13") (pin "1") (pinfunction "1_1") (pintype "passive"))
      (node (ref "X1") (pin "P$1") (pinfunction "P$1_P$1") (pintype "bidirectional"))
    )
    (net (code "13") (name "Net-(F2-2-Pad2A)") (class "Default")
      (node (ref "F2") (pin "2A") (pinfunction "2_2A") (pintype "passive"))
      (node (ref "F2") (pin "2B") (pinfunction "2_2B") (pintype "passive"))
      (node (ref "J11") (pin "A1") (pinfunction "1_A1") (pintype "passive"))
      (node (ref "J11") (pin "A2") (pinfunction "1_A2") (pintype "passive"))
    )
    (net (code "14") (name "Net-(F3-1-Pad1A)") (class "Default")
      (node (ref "F3") (pin "1A") (pinfunction "1_1A") (pintype "passive"))
      (node (ref "F3") (pin "1B") (pinfunction "1_1B") (pintype "passive"))
      (node (ref "J9") (pin "A1") (pinfunction "1_A1") (pintype "passive"))
      (node (ref "J9") (pin "A2") (pinfunction "1_A2") (pintype "passive"))
    )
    (net (code "15") (name "Net-(F3-2-Pad2A)") (class "Default")
      (node (ref "F3") (pin "2A") (pinfunction "2_2A") (pintype "passive"))
      (node (ref "F3") (pin "2B") (pinfunction "2_2B") (pintype "passive"))
      (node (ref "R39") (pin "2") (pinfunction "2_2") (pintype "passive"))
      (node (ref "T2") (pin "A2") (pinfunction "A2_A2") (pintype "passive"))
    )
    (net (code "16") (name "Net-(J3-1-PadA1)") (class "Default")
      (node (ref "J3") (pin "A1") (pinfunction "1_A1") (pintype "passive"))
      (node (ref "J3") (pin "A2") (pinfunction "1_A2") (pintype "passive"))
      (node (ref "SJ2") (pin "2") (pinfunction "2_2") (pintype "passive"))
    )
    (net (code "17") (name "Net-(J4-4)") (class "Default")
      (node (ref "J4") (pin "3") (pinfunction "4_3") (pintype "passive"))
      (node (ref "J5") (pin "3") (pinfunction "4_3") (pintype "passive"))
      (node (ref "R29") (pin "1") (pinfunction "1_1") (pintype "passive"))
    )
    (net (code "18") (name "Net-(J6-1)") (class "Default")
      (node (ref "J6") (pin "6") (pinfunction "1_6") (pintype "passive"))
      (node (ref "R35") (pin "1") (pinfunction "1_1") (pintype "passive"))
      (node (ref "R4") (pin "1") (pinfunction "1_1") (pintype "passive"))
      (node (ref "R9") (pin "2") (pinfunction "2_2") (pintype "passive"))
    )
    (net (code "19") (name "Net-(J6-5)") (class "Default")
      (node (ref "D3") (pin "A") (pinfunction "A_A") (pintype "passive"))
      (node (ref "D4") (pin "C") (pinfunction "C_C") (pintype "passive"))
      (node (ref "J6") (pin "2") (pinfunction "5_2") (pintype "passive"))
      (node (ref "R34") (pin "2") (pinfunction "2_2") (pintype "passive"))
    )
    (net (code "20") (name "Net-(J6-6)") (class "Default")
      (node (ref "D5") (pin "A") (pinfunction "A_A") (pintype "passive"))
      (node (ref "D6") (pin "C") (pinfunction "C_C") (pintype "passive"))
      (node (ref "J6") (pin "1") (pinfunction "6_1") (pintype "passive"))
      (node (ref "R34") (pin "1") (pinfunction "1_1") (pintype "passive"))
    )
    (net (code "21") (name "Net-(J7-1)") (class "Default")
      (node (ref "C10") (pin "1") (pinfunction "1_1") (pintype "passive"))
      (node (ref "J7") (pin "6") (pinfunction "1_6") (pintype "passive"))
      (node (ref "R23") (pin "2") (pinfunction "2_2") (pintype "passive"))
      (node (ref "R24") (pin "2") (pinfunction "2_2") (pintype "passive"))
    )
    (net (code "22") (name "Net-(J7-5)") (class "Default")
      (node (ref "J7") (pin "2") (pinfunction "5_2") (pintype "passive"))
      (node (ref "Q2") (pin "3") (pinfunction "C_3") (pintype "passive"))
    )
    (net (code "23") (name "Net-(J8-1-PadA1)") (class "Default")
      (node (ref "J8") (pin "A1") (pinfunction "1_A1") (pintype "passive"))
      (node (ref "J8") (pin "A2") (pinfunction "1_A2") (pintype "passive"))
      (node (ref "T2") (pin "A1") (pinfunction "A1_A1") (pintype "passive"))
    )
    (net (code "24") (name "Net-(J12-1-PadA1)") (class "Default")
      (node (ref "J12") (pin "A1") (pinfunction "1_A1") (pintype "passive"))
      (node (ref "J12") (pin "A2") (pinfunction "1_A2") (pintype "passive"))
      (node (ref "T1") (pin "A1") (pinfunction "A1_A1") (pintype "passive"))
    )
    (net (code "25") (name "Net-(J14-1-PadA1)") (class "Default")
      (node (ref "J14") (pin "A1") (pinfunction "1_A1") (pintype "passive"))
      (node (ref "J14") (pin "A2") (pinfunction "1_A2") (pintype "passive"))
      (node (ref "R30") (pin "1") (pinfunction "1_1") (pintype "passive"))
      (node (ref "R36") (pin "2") (pinfunction "2_2") (pintype "passive"))
      (node (ref "T1") (pin "A2") (pinfunction "A2_A2") (pintype "passive"))
      (node (ref "X1") (pin "P$4") (pinfunction "P$4_P$4") (pintype "bidirectional"))
    )
    (net (code "26") (name "Net-(LCD1-CONT)") (class "Default")
      (node (ref "LCD1") (pin "3") (pinfunction "CONT_3") (pintype "input"))
      (node (ref "R16") (pin "2") (pinfunction "2_2") (pintype "passive"))
    )
    (net (code "27") (name "Net-(LED2-PadA)") (class "Default")
      (node (ref "LED2") (pin "A") (pinfunction "A_A") (pintype "passive"))
      (node (ref "R2") (pin "1") (pinfunction "1_1") (pintype "passive"))
    )
    (net (code "28") (name "Net-(OK1-A)") (class "Default")
      (node (ref "OK1") (pin "1") (pinfunction "A_1") (pintype "passive"))
      (node (ref "R32") (pin "2") (pinfunction "2_2") (pintype "passive"))
    )
    (net (code "29") (name "Net-(OK1-C)") (class "Default")
      (node (ref "OK1") (pin "2") (pinfunction "C_2") (pintype "passive"))
      (node (ref "Q1") (pin "3") (pinfunction "C_3") (pintype "passive"))
    )
    (net (code "30") (name "Net-(OK2-A)") (class "Default")
      (node (ref "OK2") (pin "1") (pinfunction "A_1") (pintype "passive"))
      (node (ref "R37") (pin "2") (pinfunction "2_2") (pintype "passive"))
    )
    (net (code "31") (name "Net-(OK2-A1)") (class "Default")
      (node (ref "OK2") (pin "4") (pinfunction "A1_4") (pintype "passive"))
      (node (ref "T1") (pin "G") (pinfunction "G_G") (pintype "passive"))
    )
    (net (code "32") (name "Net-(OK2-A2)") (class "Default")
      (node (ref "OK2") (pin "6") (pinfunction "A2_6") (pintype "passive"))
      (node (ref "R36") (pin "1") (pinfunction "1_1") (pintype "passive"))
    )
    (net (code "33") (name "Net-(OK3-A)") (class "Default")
      (node (ref "OK3") (pin "1") (pinfunction "A_1") (pintype "passive"))
      (node (ref "R10") (pin "2") (pinfunction "2_2") (pintype "passive"))
    )
    (net (code "34") (name "Net-(OK3-A1)") (class "Default")
      (node (ref "OK3") (pin "4") (pinfunction "A1_4") (pintype "passive"))
      (node (ref "T2") (pin "G") (pinfunction "G_G") (pintype "passive"))
    )
    (net (code "35") (name "Net-(OK3-A2)") (class "Default")
      (node (ref "OK3") (pin "6") (pinfunction "A2_6") (pintype "passive"))
      (node (ref "R39") (pin "1") (pinfunction "1_1") (pintype "passive"))
    )
    (net (code "36") (name "Net-(Q1-B)") (class "Default")
      (node (ref "D10") (pin "A") (pinfunction "A_A") (pintype "passive"))
      (node (ref "D11") (pin "C") (pinfunction "C_C") (pintype "passive"))
      (node (ref "D9") (pin "A") (pinfunction "A_A") (pintype "passive"))
      (node (ref "Q1") (pin "1") (pinfunction "B_1") (pintype "passive"))
      (node (ref "R31") (pin "1") (pinfunction "1_1") (pintype "passive"))
    )
    (net (code "37") (name "Net-(Q1-E)") (class "Default")
      (node (ref "C14") (pin "-") (pinfunction "-_-") (pintype "passive"))
      (node (ref "D11") (pin "A") (pinfunction "A_A") (pintype "passive"))
      (node (ref "Q1") (pin "2") (pinfunction "E_2") (pintype "passive"))
    )
    (net (code "38") (name "Net-(Q2-B)") (class "Default")
      (node (ref "Q2") (pin "1") (pinfunction "B_1") (pintype "passive"))
      (node (ref "R12") (pin "2") (pinfunction "2_2") (pintype "passive"))
    )
    (net (code "39") (name "Net-(Q4-B)") (class "Default")
      (node (ref "Q4") (pin "1") (pinfunction "B_1") (pintype "passive"))
      (node (ref "R22") (pin "2") (pinfunction "2_2") (pintype "passive"))
    )
    (net (code "40") (name "Net-(Q4-C)") (class "Default")
      (node (ref "L2") (pin "1") (pinfunction "1_1") (pintype "passive"))
      (node (ref "Q4") (pin "3") (pinfunction "C_3") (pintype "passive"))
      (node (ref "SG1") (pin "2") (pinfunction "2_2") (pintype "passive"))
    )
    (net (code "41") (name "Net-(R18-Pad1)") (class "Default")
      (node (ref "R18") (pin "1") (pinfunction "1_1") (pintype "passive"))
      (node (ref "R19") (pin "2") (pinfunction "2_2") (pintype "passive"))
      (node (ref "SW2") (pin "1") (pinfunction "1_1") (pintype "passive"))
      (node (ref "SW2") (pin "2") (pinfunction "2_2") (pintype "passive"))
    )
    (net (code "42") (name "Net-(R19-Pad1)") (class "Default")
      (node (ref "R19") (pin "1") (pinfunction "1_1") (pintype "passive"))
      (node (ref "R20") (pin "2") (pinfunction "2_2") (pintype "passive"))
      (node (ref "SW3") (pin "1") (pinfunction "1_1") (pintype "passive"))
      (node (ref "SW3") (pin "2") (pinfunction "2_2") (pintype "passive"))
    )
    (net (code "43") (name "Net-(R20-Pad1)") (class "Default")
      (node (ref "R20") (pin "1") (pinfunction "1_1") (pintype "passive"))
      (node (ref "R21") (pin "2") (pinfunction "2_2") (pintype "passive"))
      (node (ref "SW4") (pin "1") (pinfunction "1_1") (pintype "passive"))
      (node (ref "SW4") (pin "2") (pinfunction "2_2") (pintype "passive"))
    )
    (net (code "44") (name "Net-(R21-Pad1)") (class "Default")
      (node (ref "R21") (pin "1") (pinfunction "1_1") (pintype "passive"))
      (node (ref "SW5") (pin "1") (pinfunction "1_1") (pintype "passive"))
      (node (ref "SW5") (pin "2") (pinfunction "2_2") (pintype "passive"))
    )
    (net (code "45") (name "Net-(R25-Pad1)") (class "Default")
      (node (ref "R25") (pin "1") (pinfunction "1_1") (pintype "passive"))
      (node (ref "R28") (pin "1") (pinfunction "1_1") (pintype "passive"))
      (node (ref "SW1") (pin "B") (pinfunction "B_B") (pintype "passive"))
    )
    (net (code "46") (name "Net-(R26-Pad1)") (class "Default")
      (node (ref "R26") (pin "1") (pinfunction "1_1") (pintype "passive"))
      (node (ref "R27") (pin "1") (pinfunction "1_1") (pintype "passive"))
      (node (ref "SW1") (pin "A") (pinfunction "A_A") (pintype "passive"))
    )
    (net (code "47") (name "Net-(U1-AREF)") (class "Default")
      (node (ref "C6") (pin "2") (pinfunction "2_2") (pintype "passive"))
      (node (ref "L1") (pin "2") (pinfunction "2_2") (pintype "passive"))
      (node (ref "U1") (pin "23") (pinfunction "AVCC_23") (pintype "power_in"))
      (node (ref "U1") (pin "25") (pinfunction "AREF_25") (pintype "passive"))
    )
    (net (code "48") (name "Net-(U3A-+IN)") (class "Default")
      (node (ref "R4") (pin "2") (pinfunction "2_2") (pintype "passive"))
      (node (ref "R8") (pin "1") (pinfunction "1_1") (pintype "passive"))
      (node (ref "U3") (pin "3") (pinfunction "+IN_3") (pintype "input"))
    )
    (net (code "49") (name "Net-(U3A-OUT)") (class "Default")
      (node (ref "R6") (pin "2") (pinfunction "2_2") (pintype "passive"))
      (node (ref "R7") (pin "2") (pinfunction "2_2") (pintype "passive"))
      (node (ref "R8") (pin "2") (pinfunction "2_2") (pintype "passive"))
      (node (ref "U3") (pin "1") (pinfunction "OUT_1") (pintype "output"))
    )
    (net (code "50") (name "Net-(X1-PadP$2)") (class "Default")
      (node (ref "X1") (pin "P$2") (pinfunction "P$2_P$2") (pintype "bidirectional"))
      (node (ref "X1") (pin "P$3") (pinfunction "P$3_P$3") (pintype "bidirectional"))
    )
    (net (code "51") (name "Net-(X1-PadP$6)") (class "Default")
      (node (ref "X1") (pin "P$6") (pinfunction "P$6_P$6") (pintype "bidirectional"))
      (node (ref "X1") (pin "P$8") (pinfunction "P$8_P$8") (pintype "bidirectional"))
    )
    (net (code "52") (name "PB0") (class "Default")
      (node (ref "J4") (pin "4") (pinfunction "3_4") (pintype "passive"))
      (node (ref "J5") (pin "5") (pinfunction "2_5") (pintype "passive"))
      (node (ref "U1") (pin "12") (pinfunction "PB0(MISO/PSCOUT20)_12") (pintype "bidirectional"))
    )
    (net (code "53") (name "PB1") (class "Default")
      (node (ref "J4") (pin "5") (pinfunction "2_5") (pintype "passive"))
      (node (ref "J5") (pin "4") (pinfunction "3_4") (pintype "passive"))
      (node (ref "U1") (pin "13") (pinfunction "PB1(MOSI/PSCOUT21)_13") (pintype "bidirectional"))
    )
    (net (code "54") (name "PB2") (class "Default")
      (node (ref "OK1") (pin "4") (pinfunction "COL_4") (pintype "passive"))
      (node (ref "R33") (pin "1") (pinfunction "1_1") (pintype "passive"))
      (node (ref "U1") (pin "20") (pinfunction "PB2(ADC5/INT1)_20") (pintype "bidirectional"))
    )
    (net (code "55") (name "PB3") (class "Default")
      (node (ref "LCD1") (pin "11") (pinfunction "D4_11") (pintype "input"))
      (node (ref "U1") (pin "27") (pinfunction "PB3(AMP0-)_27") (pintype "bidirectional"))
    )
    (net (code "56") (name "PB4") (class "Default")
      (node (ref "LCD1") (pin "12") (pinfunction "D5_12") (pintype "input"))
      (node (ref "U1") (pin "28") (pinfunction "PB4(AMP0+)_28") (pintype "bidirectional"))
    )
    (net (code "57") (name "PB5") (class "Default")
      (node (ref "LCD1") (pin "13") (pinfunction "D6_13") (pintype "input"))
      (node (ref "U1") (pin "30") (pinfunction "PB5(ADC6/INT2)_30") (pintype "bidirectional"))
    )
    (net (code "58") (name "PB6") (class "Default")
      (node (ref "LCD1") (pin "14") (pinfunction "D7_14") (pintype "input"))
      (node (ref "U1") (pin "31") (pinfunction "PB6(ADC7/PSCOUT11/ICP1B)_31") (pintype "bidirectional"))
    )
    (net (code "59") (name "PB7") (class "Default")
      (node (ref "LCD1") (pin "6") (pinfunction "E_6") (pintype "input"))
      (node (ref "U1") (pin "32") (pinfunction "PB7(ADC4/PSCOUT01/SCK)_32") (pintype "bidirectional"))
    )
    (net (code "60") (name "PC0") (class "Default")
      (node (ref "C13") (pin "1") (pinfunction "1_1") (pintype "passive"))
      (node (ref "R28") (pin "2") (pinfunction "2_2") (pintype "passive"))
      (node (ref "U1") (pin "2") (pinfunction "PC0(INT3/PSCOUT10)_2") (pintype "bidirectional"))
    )
    (net (code "61") (name "PC1") (class "Default")
      (node (ref "R7") (pin "1") (pinfunction "1_1") (pintype "passive"))
      (node (ref "U1") (pin "7") (pinfunction "PC1(PSCIN1/OC1B)_7") (pintype "bidirectional"))
    )
    (net (code "62") (name "PC2") (class "Default")
      (node (ref "R10") (pin "1") (pinfunction "1_1") (pintype "passive"))
      (node (ref "U1") (pin "10") (pinfunction "PC2(T0/PSCOUT22)_10") (pintype "bidirectional"))
    )
    (net (code "63") (name "PC3") (class "Default")
      (node (ref "J10") (pin "2") (pinfunction "5_2") (pintype "passive"))
      (node (ref "R12") (pin "1") (pinfunction "1_1") (pintype "passive"))
      (node (ref "U1") (pin "11") (pinfunction "PC3(T1/PSCOUT23)_11") (pintype "bidirectional"))
    )
    (net (code "64") (name "PC4") (class "Default")
      (node (ref "C11") (pin "1") (pinfunction "1_1") (pintype "passive"))
      (node (ref "D3") (pin "C") (pinfunction "C_C") (pintype "passive"))
      (node (ref "D5") (pin "C") (pinfunction "C_C") (pintype "passive"))
      (node (ref "R14") (pin "2") (pinfunction "2_2") (pintype "passive"))
      (node (ref "U1") (pin "21") (pinfunction "PC4(ADC8/AMP1-)_21") (pintype "bidirectional"))
    )
    (net (code "65") (name "PC5") (class "Default")
      (node (ref "C9") (pin "+") (pinfunction "+_+") (pintype "passive"))
      (node (ref "D1") (pin "C") (pinfunction "C_C") (pintype "passive"))
      (node (ref "R5") (pin "2") (pinfunction "2_2") (pintype "passive"))
      (node (ref "U1") (pin "22") (pinfunction "PC5(ADC9/AMP1+)_22") (pintype "bidirectional"))
    )
    (net (code "66") (name "PC6") (class "Default")
      (node (ref "R17") (pin "1") (pinfunction "1_1") (pintype "passive"))
      (node (ref "R18") (pin "2") (pinfunction "2_2") (pintype "passive"))
      (node (ref "SW1") (pin "W") (pinfunction "2_W") (pintype "passive"))
      (node (ref "U1") (pin "26") (pinfunction "PC6(ADC10/ACMP1)_26") (pintype "bidirectional"))
    )
    (net (code "67") (name "PC7") (class "Default")
      (node (ref "LCD1") (pin "4") (pinfunction "RS_4") (pintype "input"))
      (node (ref "U1") (pin "29") (pinfunction "PC7(D2A)_29") (pintype "bidirectional"))
    )
    (net (code "68") (name "PD0") (class "Default")
      (node (ref "R22") (pin "1") (pinfunction "1_1") (pintype "passive"))
      (node (ref "U1") (pin "1") (pinfunction "PD0(PSCOUT00/XCK/SS_A)_1") (pintype "bidirectional"))
    )
    (net (code "69") (name "PD1") (class "Default")
      (node (ref "C12") (pin "1") (pinfunction "1_1") (pintype "passive"))
      (node (ref "R27") (pin "2") (pinfunction "2_2") (pintype "passive"))
      (node (ref "U1") (pin "4") (pinfunction "PD1(PSCIN0/CLKO)_4") (pintype "bidirectional"))
    )
    (net (code "70") (name "PD2") (class "Default")
      (node (ref "C4") (pin "1") (pinfunction "1_1") (pintype "passive"))
      (node (ref "J2") (pin "1") (pinfunction "S_1") (pintype "passive"))
      (node (ref "R29") (pin "2") (pinfunction "2_2") (pintype "passive"))
      (node (ref "U1") (pin "5") (pinfunction "PD2(PSCIN2/OC1A/MISO_A)_5") (pintype "bidirectional"))
    )
    (net (code "71") (name "PD3") (class "Default")
      (node (ref "J2") (pin "4") (pinfunction "S_4") (pintype "passive"))
      (node (ref "U1") (pin "6") (pinfunction "PD3(TXD/DALI/OC0A/SS/MOSI_A)_6") (pintype "bidirectional"))
    )
    (net (code "72") (name "PD4") (class "Default")
      (node (ref "J2") (pin "3") (pinfunction "S_3") (pintype "passive"))
      (node (ref "U1") (pin "16") (pinfunction "PD4(ADC1/RXD/DALI/ICP1A/SCK_A)_16") (pintype "bidirectional"))
    )
    (net (code "73") (name "PD5") (class "Default")
      (node (ref "D16") (pin "C") (pinfunction "C_C") (pintype "passive"))
      (node (ref "J10") (pin "4") (pinfunction "3_4") (pintype "passive"))
      (node (ref "R1") (pin "2") (pinfunction "2_2") (pintype "passive"))
      (node (ref "R38") (pin "1") (pinfunction "1_1") (pintype "passive"))
      (node (ref "U1") (pin "17") (pinfunction "PD5(ADC2/ACMP2)_17") (pintype "bidirectional"))
    )
    (net (code "74") (name "PD6") (class "Default")
      (node (ref "R23") (pin "1") (pinfunction "1_1") (pintype "passive"))
      (node (ref "U1") (pin "18") (pinfunction "PD6(ADC3/ACMPM/INT0)_18") (pintype "bidirectional"))
    )
    (net (code "75") (name "PD7") (class "Default")
      (node (ref "J10") (pin "3") (pinfunction "4_3") (pintype "passive"))
      (node (ref "R37") (pin "1") (pinfunction "1_1") (pintype "passive"))
      (node (ref "U1") (pin "19") (pinfunction "PD7(ACMP0)_19") (pintype "bidirectional"))
    )
    (net (code "76") (name "PE1") (class "Default")
      (node (ref "J7") (pin "4") (pinfunction "3_4") (pintype "passive"))
      (node (ref "U1") (pin "14") (pinfunction "PE1(OC0B/XTAL1)_14") (pintype "bidirectional"))
    )
    (net (code "77") (name "PE2") (class "Default")
      (node (ref "J10") (pin "5") (pinfunction "2_5") (pintype "passive"))
      (node (ref "U1") (pin "15") (pinfunction "PE2(ADC0/XTAL2)_15") (pintype "bidirectional"))
    )
    (net (code "78") (name "PG") (class "Default")
      (node (ref "J1") (pin "8") (pinfunction "S_8") (pintype "passive"))
      (node (ref "R2") (pin "2") (pinfunction "2_2") (pintype "passive"))
    )
    (net (code "79") (name "PS_ON") (class "Default")
      (node (ref "J1") (pin "14") (pinfunction "S_14") (pintype "passive"))
      (node (ref "J7") (pin "1") (pinfunction "6_1") (pintype "passive"))
    )
    (net (code "80") (name "RESET") (class "Default")
      (node (ref "J2") (pin "5") (pinfunction "S_5") (pintype "passive"))
      (node (ref "R3") (pin "2") (pinfunction "2_2") (pintype "passive"))
      (node (ref "U1") (pin "3") (pinfunction "PE0(RESET/OCD)_3") (pintype "bidirectional"))
    )
    (net (code "81") (name "unconnected-(R16-Pad1)") (class "Default")
      (node (ref "R16") (pin "1") (pinfunction "1_1") (pintype "passive"))
    )
    (net (code "82") (name "unconnected-(U3B-OUT-Pad7)") (class "Default")
      (node (ref "U3") (pin "7") (pinfunction "OUT_7") (pintype "output"))
    )
  )
)
